# anti-spark-pcb.net
KiCad netlist of a schematic drawn in EAGLE
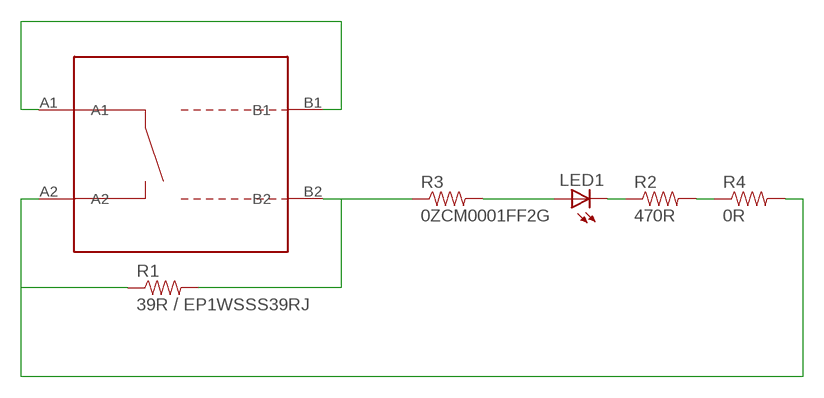
[diagram p0: schematic, sheet 1]

(export (version "E")
  (design (tool "Eeschema 10.0.6"))
  (components
    (comp (ref "LED1")
      (value "LED1206")
      (footprint "eagle-import:LED-1206")
      (libsource (lib "eagle-import") (part "LED1206"))
    )
    (comp (ref "PCB1")
      (value "KAKE-SWITCH-PCB")
      (footprint "eagle-import:KAKE-SWITCH-PCB")
      (libsource (lib "eagle-import") (part "KAKE-SWITCH-PCB"))
    )
    (comp (ref "R1")
      (value "39R / EP1WSSS39RJ")
      (footprint "eagle-import:AXIAL-0.6")
      (libsource (lib "eagle-import") (part "RESISTORPTH-1W"))
    )
    (comp (ref "R2")
      (value "470R")
      (footprint "eagle-import:0603-RES")
      (libsource (lib "eagle-import") (part "RESISTOR0603-RES"))
    )
    (comp (ref "R3")
      (value "0ZCM0001FF2G")
      (footprint "eagle-import:0603-RES")
      (libsource (lib "eagle-import") (part "RESISTOR0603-RES"))
    )
    (comp (ref "R4")
      (value "0R")
      (footprint "eagle-import:0603-RES")
      (libsource (lib "eagle-import") (part "RESISTOR0603-RES"))
    )
  )
  (nets
    (net (code "1") (name "Net-(LED1-PadA)") (class "Default")
      (node (ref "LED1") (pin "A") (pinfunction "A_A") (pintype "passive"))
      (node (ref "R3") (pin "2") (pinfunction "2_2") (pintype "passive"))
    )
    (net (code "2") (name "Net-(LED1-PadC)") (class "Default")
      (node (ref "LED1") (pin "C") (pinfunction "C_C") (pintype "passive"))
      (node (ref "R2") (pin "1") (pinfunction "1_1") (pintype "passive"))
    )
    (net (code "3") (name "Net-(PCB1-PadA1)") (class "Default")
      (node (ref "PCB1") (pin "A1") (pinfunction "A1_A1") (pintype "bidirectional"))
      (node (ref "PCB1") (pin "B1") (pinfunction "B1_B1") (pintype "bidirectional"))
    )
    (net (code "4") (name "Net-(R1-1)") (class "Default")
      (node (ref "PCB1") (pin "A2") (pinfunction "A2_A2") (pintype "bidirectional"))
      (node (ref "R1") (pin "P$1") (pinfunction "1_P$1") (pintype "passive"))
      (node (ref "R4") (pin "2") (pinfunction "2_2") (pintype "passive"))
    )
    (net (code "5") (name "Net-(R1-2)") (class "Default")
      (node (ref "PCB1") (pin "B2") (pinfunction "B2_B2") (pintype "bidirectional"))
      (node (ref "R1") (pin "P$2") (pinfunction "2_P$2") (pintype "passive"))
      (node (ref "R3") (pin "1") (pinfunction "1_1") (pintype "passive"))
    )
    (net (code "6") (name "Net-(R2-Pad2)") (class "Default")
      (node (ref "R2") (pin "2") (pinfunction "2_2") (pintype "passive"))
      (node (ref "R4") (pin "1") (pinfunction "1_1") (pintype "passive"))
    )
  )
)
